# nbedmbed_mini.net
KiCad netlist of a schematic drawn in EAGLE
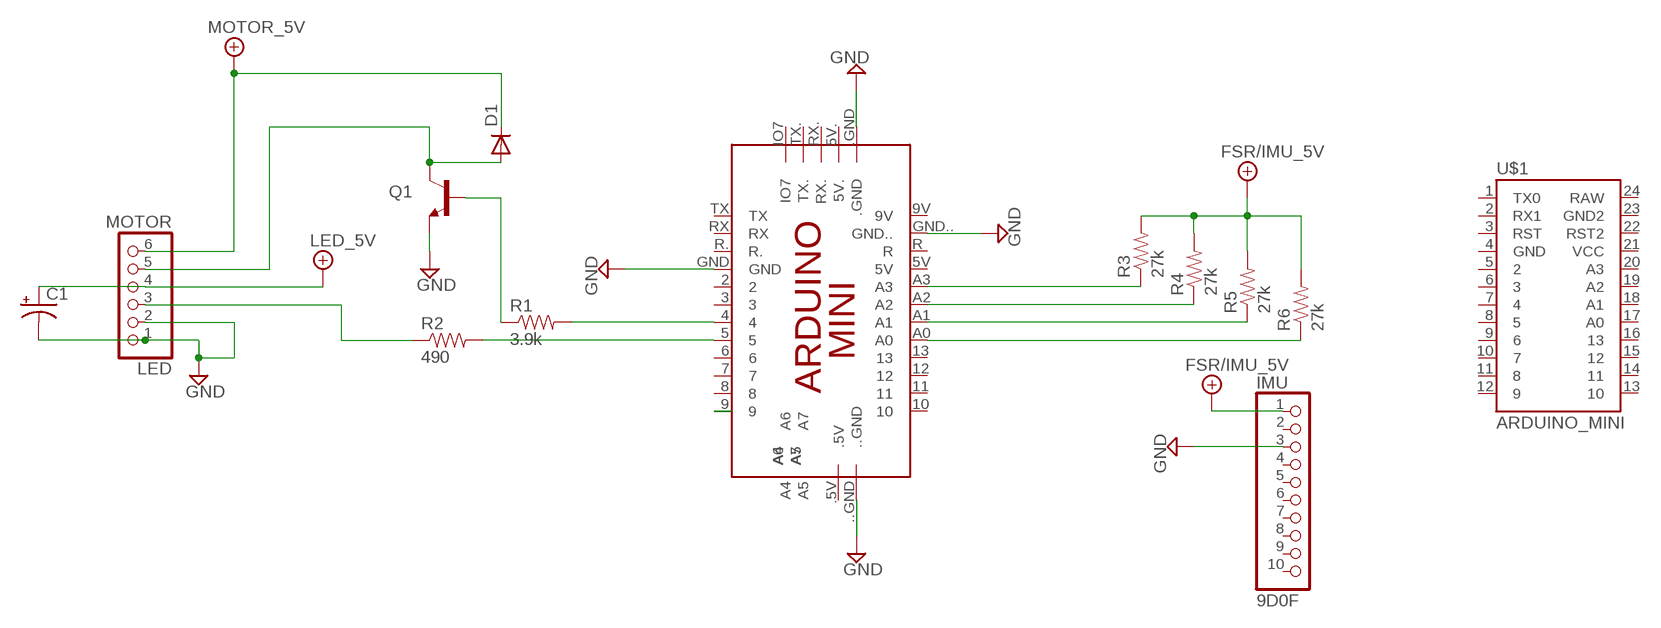
[diagram p0: schematic, sheet 1]

(export (version "E")
  (design (tool "Eeschema 10.0.6"))
  (components
    (comp (ref "C1")
      (value "CAP_POLPTH1")
      (footprint "eagle-import:CPOL-RADIAL-100UF-25V")
      (libsource (lib "eagle-import") (part "CAP_POLPTH1"))
    )
    (comp (ref "D1")
      (value "DIODE1N4148")
      (footprint "eagle-import:DIODE-1N4148")
      (libsource (lib "eagle-import") (part "DIODE1N4148"))
    )
    (comp (ref "IMU")
      (value "9D0F")
      (footprint "eagle-import:1X10-BIG")
      (libsource (lib "eagle-import") (part "PINHD-1X10"))
    )
    (comp (ref "LED")
      (value "MOTOR")
      (footprint "eagle-import:1X06-BIG")
      (libsource (lib "eagle-import") (part "PINHD-1X6B"))
    )
    (comp (ref "PCB1")
      (value "ARDUINO_MINI")
      (footprint "eagle-import:ARDUINO_MINI")
      (libsource (lib "eagle-import") (part "ARDUINO_MINI"))
    )
    (comp (ref "Q1")
      (value "TRANSISTOR_NPNTO-92-AMMO")
      (footprint "eagle-import:TO-92-AMMO")
      (libsource (lib "eagle-import") (part "TRANSISTOR_NPNTO-92-AMMO"))
    )
    (comp (ref "R1")
      (value "3.9k")
      (footprint "eagle-import:1_6W-RES")
      (libsource (lib "eagle-import") (part "RESISTORPTH-1/6W"))
    )
    (comp (ref "R2")
      (value "490")
      (footprint "eagle-import:1_6W-RES")
      (libsource (lib "eagle-import") (part "RESISTORPTH-1/6W"))
    )
    (comp (ref "R3")
      (value "27k")
      (footprint "eagle-import:1_6W-RES")
      (libsource (lib "eagle-import") (part "RESISTORPTH-1/6W"))
    )
    (comp (ref "R4")
      (value "27k")
      (footprint "eagle-import:1_6W-RES")
      (libsource (lib "eagle-import") (part "RESISTORPTH-1/6W"))
    )
    (comp (ref "R5")
      (value "27k")
      (footprint "eagle-import:1_6W-RES")
      (libsource (lib "eagle-import") (part "RESISTORPTH-1/6W"))
    )
    (comp (ref "R6")
      (value "27k")
      (footprint "eagle-import:1_6W-RES")
      (libsource (lib "eagle-import") (part "RESISTORPTH-1/6W"))
    )
    (comp (ref "U$1")
      (value "ARDUINO_MINI")
      (footprint "eagle-import:ARDUINO_MINI")
      (libsource (lib "eagle-import") (part "SparkFun-Boards_ARDUINO_MINI"))
    )
  )
  (nets
    (net (code "1") (name "FSR{slash}IMU_5V") (class "Default")
      (node (ref "IMU") (pin "1") (pinfunction "1_1") (pintype "passive"))
      (node (ref "R3") (pin "2") (pinfunction "2_2") (pintype "passive"))
      (node (ref "R4") (pin "2") (pinfunction "2_2") (pintype "passive"))
      (node (ref "R5") (pin "2") (pinfunction "2_2") (pintype "passive"))
      (node (ref "R6") (pin "2") (pinfunction "2_2") (pintype "passive"))
    )
    (net (code "2") (name "GND") (class "Default")
      (node (ref "C1") (pin "2") (pinfunction "-_2") (pintype "passive"))
      (node (ref "IMU") (pin "3") (pinfunction "3_3") (pintype "passive"))
      (node (ref "LED") (pin "1") (pinfunction "1_1") (pintype "passive"))
      (node (ref "LED") (pin "2") (pinfunction "2_2") (pintype "passive"))
      (node (ref "PCB1") (pin "..GND") (pinfunction "..GND_..GND") (pintype "bidirectional"))
      (node (ref "PCB1") (pin ".GND") (pinfunction ".GND_.GND") (pintype "bidirectional"))
      (node (ref "PCB1") (pin "GND") (pinfunction "GND_GND") (pintype "bidirectional"))
      (node (ref "PCB1") (pin "GND..") (pinfunction "GND.._GND..") (pintype "bidirectional"))
      (node (ref "Q1") (pin "1") (pinfunction "E_1") (pintype "passive"))
    )
    (net (code "3") (name "LED_5V") (class "Default")
      (node (ref "C1") (pin "1") (pinfunction "+_1") (pintype "passive"))
      (node (ref "LED") (pin "4") (pinfunction "4_4") (pintype "passive"))
    )
    (net (code "4") (name "MOTOR_5V") (class "Default")
      (node (ref "D1") (pin "C") (pinfunction "C_C") (pintype "passive"))
      (node (ref "LED") (pin "6") (pinfunction "6_6") (pintype "passive"))
    )
    (net (code "5") (name "Net-(LED-Pad3)") (class "Default")
      (node (ref "LED") (pin "3") (pinfunction "3_3") (pintype "passive"))
      (node (ref "R2") (pin "1") (pinfunction "1_1") (pintype "passive"))
    )
    (net (code "6") (name "Net-(PCB1-Pad4)") (class "Default")
      (node (ref "PCB1") (pin "4") (pinfunction "4_4") (pintype "bidirectional"))
      (node (ref "R1") (pin "2") (pinfunction "2_2") (pintype "passive"))
    )
    (net (code "7") (name "Net-(PCB1-Pad5)") (class "Default")
      (node (ref "PCB1") (pin "5") (pinfunction "5_5") (pintype "bidirectional"))
      (node (ref "R2") (pin "2") (pinfunction "2_2") (pintype "passive"))
    )
    (net (code "8") (name "Net-(PCB1-PadA0)") (class "Default")
      (node (ref "PCB1") (pin "A0") (pinfunction "A0_A0") (pintype "bidirectional"))
      (node (ref "R6") (pin "1") (pinfunction "1_1") (pintype "passive"))
    )
    (net (code "9") (name "Net-(PCB1-PadA1)") (class "Default")
      (node (ref "PCB1") (pin "A1") (pinfunction "A1_A1") (pintype "bidirectional"))
      (node (ref "R5") (pin "1") (pinfunction "1_1") (pintype "passive"))
    )
    (net (code "10") (name "Net-(PCB1-PadA2)") (class "Default")
      (node (ref "PCB1") (pin "A2") (pinfunction "A2_A2") (pintype "bidirectional"))
      (node (ref "R4") (pin "1") (pinfunction "1_1") (pintype "passive"))
    )
    (net (code "11") (name "Net-(PCB1-PadA3)") (class "Default")
      (node (ref "PCB1") (pin "A3") (pinfunction "A3_A3") (pintype "bidirectional"))
      (node (ref "R3") (pin "1") (pinfunction "1_1") (pintype "passive"))
    )
    (net (code "12") (name "Net-(Q1-B)") (class "Default")
      (node (ref "Q1") (pin "2") (pinfunction "B_2") (pintype "passive"))
      (node (ref "R1") (pin "1") (pinfunction "1_1") (pintype "passive"))
    )
    (net (code "13") (name "Net-(Q1-C)") (class "Default")
      (node (ref "D1") (pin "A") (pinfunction "A_A") (pintype "passive"))
      (node (ref "LED") (pin "5") (pinfunction "5_5") (pintype "passive"))
      (node (ref "Q1") (pin "3") (pinfunction "C_3") (pintype "passive"))
    )
    (net (code "14") (name "unconnected-(IMU-Pad2)") (class "Default")
      (node (ref "IMU") (pin "2") (pinfunction "2_2") (pintype "passive"))
    )
    (net (code "15") (name "unconnected-(IMU-Pad4)") (class "Default")
      (node (ref "IMU") (pin "4") (pinfunction "4_4") (pintype "passive"))
    )
    (net (code "16") (name "unconnected-(IMU-Pad5)") (class "Default")
      (node (ref "IMU") (pin "5") (pinfunction "5_5") (pintype "passive"))
    )
    (net (code "17") (name "unconnected-(IMU-Pad6)") (class "Default")
      (node (ref "IMU") (pin "6") (pinfunction "6_6") (pintype "passive"))
    )
    (net (code "18") (name "unconnected-(IMU-Pad7)") (class "Default")
      (node (ref "IMU") (pin "7") (pinfunction "7_7") (pintype "passive"))
    )
    (net (code "19") (name "unconnected-(IMU-Pad8)") (class "Default")
      (node (ref "IMU") (pin "8") (pinfunction "8_8") (pintype "passive"))
    )
    (net (code "20") (name "unconnected-(IMU-Pad9)") (class "Default")
      (node (ref "IMU") (pin "9") (pinfunction "9_9") (pintype "passive"))
    )
    (net (code "21") (name "unconnected-(IMU-Pad10)") (class "Default")
      (node (ref "IMU") (pin "10") (pinfunction "10_10") (pintype "passive"))
    )
    (net (code "22") (name "unconnected-(PCB1-Pad.5V)") (class "Default")
      (node (ref "PCB1") (pin ".5V") (pinfunction ".5V_.5V") (pintype "bidirectional"))
    )
    (net (code "23") (name "unconnected-(PCB1-Pad2)") (class "Default")
      (node (ref "PCB1") (pin "2") (pinfunction "2_2") (pintype "bidirectional"))
    )
    (net (code "24") (name "unconnected-(PCB1-Pad3)") (class "Default")
      (node (ref "PCB1") (pin "3") (pinfunction "3_3") (pintype "bidirectional"))
    )
    (net (code "25") (name "unconnected-(PCB1-Pad5V)") (class "Default")
      (node (ref "PCB1") (pin "5V") (pinfunction "5V_5V") (pintype "bidirectional"))
    )
    (net (code "26") (name "unconnected-(PCB1-Pad5V.)") (class "Default")
      (node (ref "PCB1") (pin "5V.") (pinfunction "5V._5V.") (pintype "bidirectional"))
    )
    (net (code "27") (name "unconnected-(PCB1-Pad6)") (class "Default")
      (node (ref "PCB1") (pin "6") (pinfunction "6_6") (pintype "bidirectional"))
    )
    (net (code "28") (name "unconnected-(PCB1-Pad7)") (class "Default")
      (node (ref "PCB1") (pin "7") (pinfunction "7_7") (pintype "bidirectional"))
    )
    (net (code "29") (name "unconnected-(PCB1-Pad8)") (class "Default")
      (node (ref "PCB1") (pin "8") (pinfunction "8_8") (pintype "bidirectional"))
    )
    (net (code "30") (name "unconnected-(PCB1-Pad9)") (class "Default")
      (node (ref "PCB1") (pin "9") (pinfunction "9_9") (pintype "bidirectional"))
    )
    (net (code "31") (name "unconnected-(PCB1-Pad9V)") (class "Default")
      (node (ref "PCB1") (pin "9V") (pinfunction "9V_9V") (pintype "bidirectional"))
    )
    (net (code "32") (name "unconnected-(PCB1-Pad10)") (class "Default")
      (node (ref "PCB1") (pin "10") (pinfunction "10_10") (pintype "bidirectional"))
    )
    (net (code "33") (name "unconnected-(PCB1-Pad11)") (class "Default")
      (node (ref "PCB1") (pin "11") (pinfunction "11_11") (pintype "bidirectional"))
    )
    (net (code "34") (name "unconnected-(PCB1-Pad12)") (class "Default")
      (node (ref "PCB1") (pin "12") (pinfunction "12_12") (pintype "bidirectional"))
    )
    (net (code "35") (name "unconnected-(PCB1-Pad13)") (class "Default")
      (node (ref "PCB1") (pin "13") (pinfunction "13_13") (pintype "bidirectional"))
    )
    (net (code "36") (name "unconnected-(PCB1-PadA4)") (class "Default")
      (node (ref "PCB1") (pin "A4") (pinfunction "A4_A4") (pintype "bidirectional"))
    )
    (net (code "37") (name "unconnected-(PCB1-PadA5)") (class "Default")
      (node (ref "PCB1") (pin "A5") (pinfunction "A5_A5") (pintype "bidirectional"))
    )
    (net (code "38") (name "unconnected-(PCB1-PadA6)") (class "Default")
      (node (ref "PCB1") (pin "A6") (pinfunction "A6_A6") (pintype "bidirectional"))
    )
    (net (code "39") (name "unconnected-(PCB1-PadA7)") (class "Default")
      (node (ref "PCB1") (pin "A7") (pinfunction "A7_A7") (pintype "bidirectional"))
    )
    (net (code "40") (name "unconnected-(PCB1-PadIO7)") (class "Default")
      (node (ref "PCB1") (pin "IO7") (pinfunction "IO7_IO7") (pintype "bidirectional"))
    )
    (net (code "41") (name "unconnected-(PCB1-PadR)") (class "Default")
      (node (ref "PCB1") (pin "R") (pinfunction "R_R") (pintype "bidirectional"))
    )
    (net (code "42") (name "unconnected-(PCB1-PadR.)") (class "Default")
      (node (ref "PCB1") (pin "R.") (pinfunction "R._R.") (pintype "bidirectional"))
    )
    (net (code "43") (name "unconnected-(PCB1-PadRX)") (class "Default")
      (node (ref "PCB1") (pin "RX") (pinfunction "RX_RX") (pintype "bidirectional"))
    )
    (net (code "44") (name "unconnected-(PCB1-PadRX.)") (class "Default")
      (node (ref "PCB1") (pin "RX.") (pinfunction "RX._RX.") (pintype "bidirectional"))
    )
    (net (code "45") (name "unconnected-(PCB1-PadTX)") (class "Default")
      (node (ref "PCB1") (pin "TX") (pinfunction "TX_TX") (pintype "bidirectional"))
    )
    (net (code "46") (name "unconnected-(PCB1-PadTX.)") (class "Default")
      (node (ref "PCB1") (pin "TX.") (pinfunction "TX._TX.") (pintype "bidirectional"))
    )
    (net (code "47") (name "unconnected-(U$1-2-Pad5)") (class "Default")
      (node (ref "U$1") (pin "5") (pinfunction "2_5") (pintype "bidirectional"))
    )
    (net (code "48") (name "unconnected-(U$1-3-Pad6)") (class "Default")
      (node (ref "U$1") (pin "6") (pinfunction "3_6") (pintype "bidirectional"))
    )
    (net (code "49") (name "unconnected-(U$1-4-Pad7)") (class "Default")
      (node (ref "U$1") (pin "7") (pinfunction "4_7") (pintype "bidirectional"))
    )
    (net (code "50") (name "unconnected-(U$1-5-Pad8)") (class "Default")
      (node (ref "U$1") (pin "8") (pinfunction "5_8") (pintype "bidirectional"))
    )
    (net (code "51") (name "unconnected-(U$1-6-Pad9)") (class "Default")
      (node (ref "U$1") (pin "9") (pinfunction "6_9") (pintype "bidirectional"))
    )
    (net (code "52") (name "unconnected-(U$1-7-Pad10)") (class "Default")
      (node (ref "U$1") (pin "10") (pinfunction "7_10") (pintype "bidirectional"))
    )
    (net (code "53") (name "unconnected-(U$1-8-Pad11)") (class "Default")
      (node (ref "U$1") (pin "11") (pinfunction "8_11") (pintype "bidirectional"))
    )
    (net (code "54") (name "unconnected-(U$1-9-Pad12)") (class "Default")
      (node (ref "U$1") (pin "12") (pinfunction "9_12") (pintype "bidirectional"))
    )
    (net (code "55") (name "unconnected-(U$1-10-Pad13)") (class "Default")
      (node (ref "U$1") (pin "13") (pinfunction "10_13") (pintype "bidirectional"))
    )
    (net (code "56") (name "unconnected-(U$1-11-Pad14)") (class "Default")
      (node (ref "U$1") (pin "14") (pinfunction "11_14") (pintype "bidirectional"))
    )
    (net (code "57") (name "unconnected-(U$1-12-Pad15)") (class "Default")
      (node (ref "U$1") (pin "15") (pinfunction "12_15") (pintype "bidirectional"))
    )
    (net (code "58") (name "unconnected-(U$1-13-Pad16)") (class "Default")
      (node (ref "U$1") (pin "16") (pinfunction "13_16") (pintype "bidirectional"))
    )
    (net (code "59") (name "unconnected-(U$1-A0-Pad17)") (class "Default")
      (node (ref "U$1") (pin "17") (pinfunction "A0_17") (pintype "bidirectional"))
    )
    (net (code "60") (name "unconnected-(U$1-A1-Pad18)") (class "Default")
      (node (ref "U$1") (pin "18") (pinfunction "A1_18") (pintype "bidirectional"))
    )
    (net (code "61") (name "unconnected-(U$1-A2-Pad19)") (class "Default")
      (node (ref "U$1") (pin "19") (pinfunction "A2_19") (pintype "bidirectional"))
    )
    (net (code "62") (name "unconnected-(U$1-A3-Pad20)") (class "Default")
      (node (ref "U$1") (pin "20") (pinfunction "A3_20") (pintype "bidirectional"))
    )
    (net (code "63") (name "unconnected-(U$1-GND-Pad4)") (class "Default")
      (node (ref "U$1") (pin "4") (pinfunction "GND_4") (pintype "bidirectional"))
    )
    (net (code "64") (name "unconnected-(U$1-GND2-Pad23)") (class "Default")
      (node (ref "U$1") (pin "23") (pinfunction "GND2_23") (pintype "bidirectional"))
    )
    (net (code "65") (name "unconnected-(U$1-RAW-Pad24)") (class "Default")
      (node (ref "U$1") (pin "24") (pinfunction "RAW_24") (pintype "bidirectional"))
    )
    (net (code "66") (name "unconnected-(U$1-RST-Pad3)") (class "Default")
      (node (ref "U$1") (pin "3") (pinfunction "RST_3") (pintype "bidirectional"))
    )
    (net (code "67") (name "unconnected-(U$1-RST2-Pad22)") (class "Default")
      (node (ref "U$1") (pin "22") (pinfunction "RST2_22") (pintype "bidirectional"))
    )
    (net (code "68") (name "unconnected-(U$1-RX1-Pad2)") (class "Default")
      (node (ref "U$1") (pin "2") (pinfunction "RX1_2") (pintype "bidirectional"))
    )
    (net (code "69") (name "unconnected-(U$1-TX0-Pad1)") (class "Default")
      (node (ref "U$1") (pin "1") (pinfunction "TX0_1") (pintype "bidirectional"))
    )
    (net (code "70") (name "unconnected-(U$1-VCC-Pad21)") (class "Default")
      (node (ref "U$1") (pin "21") (pinfunction "VCC_21") (pintype "bidirectional"))
    )
  )
)
